# 04_POWER.net
KiCad netlist of a schematic drawn in Altium Designer
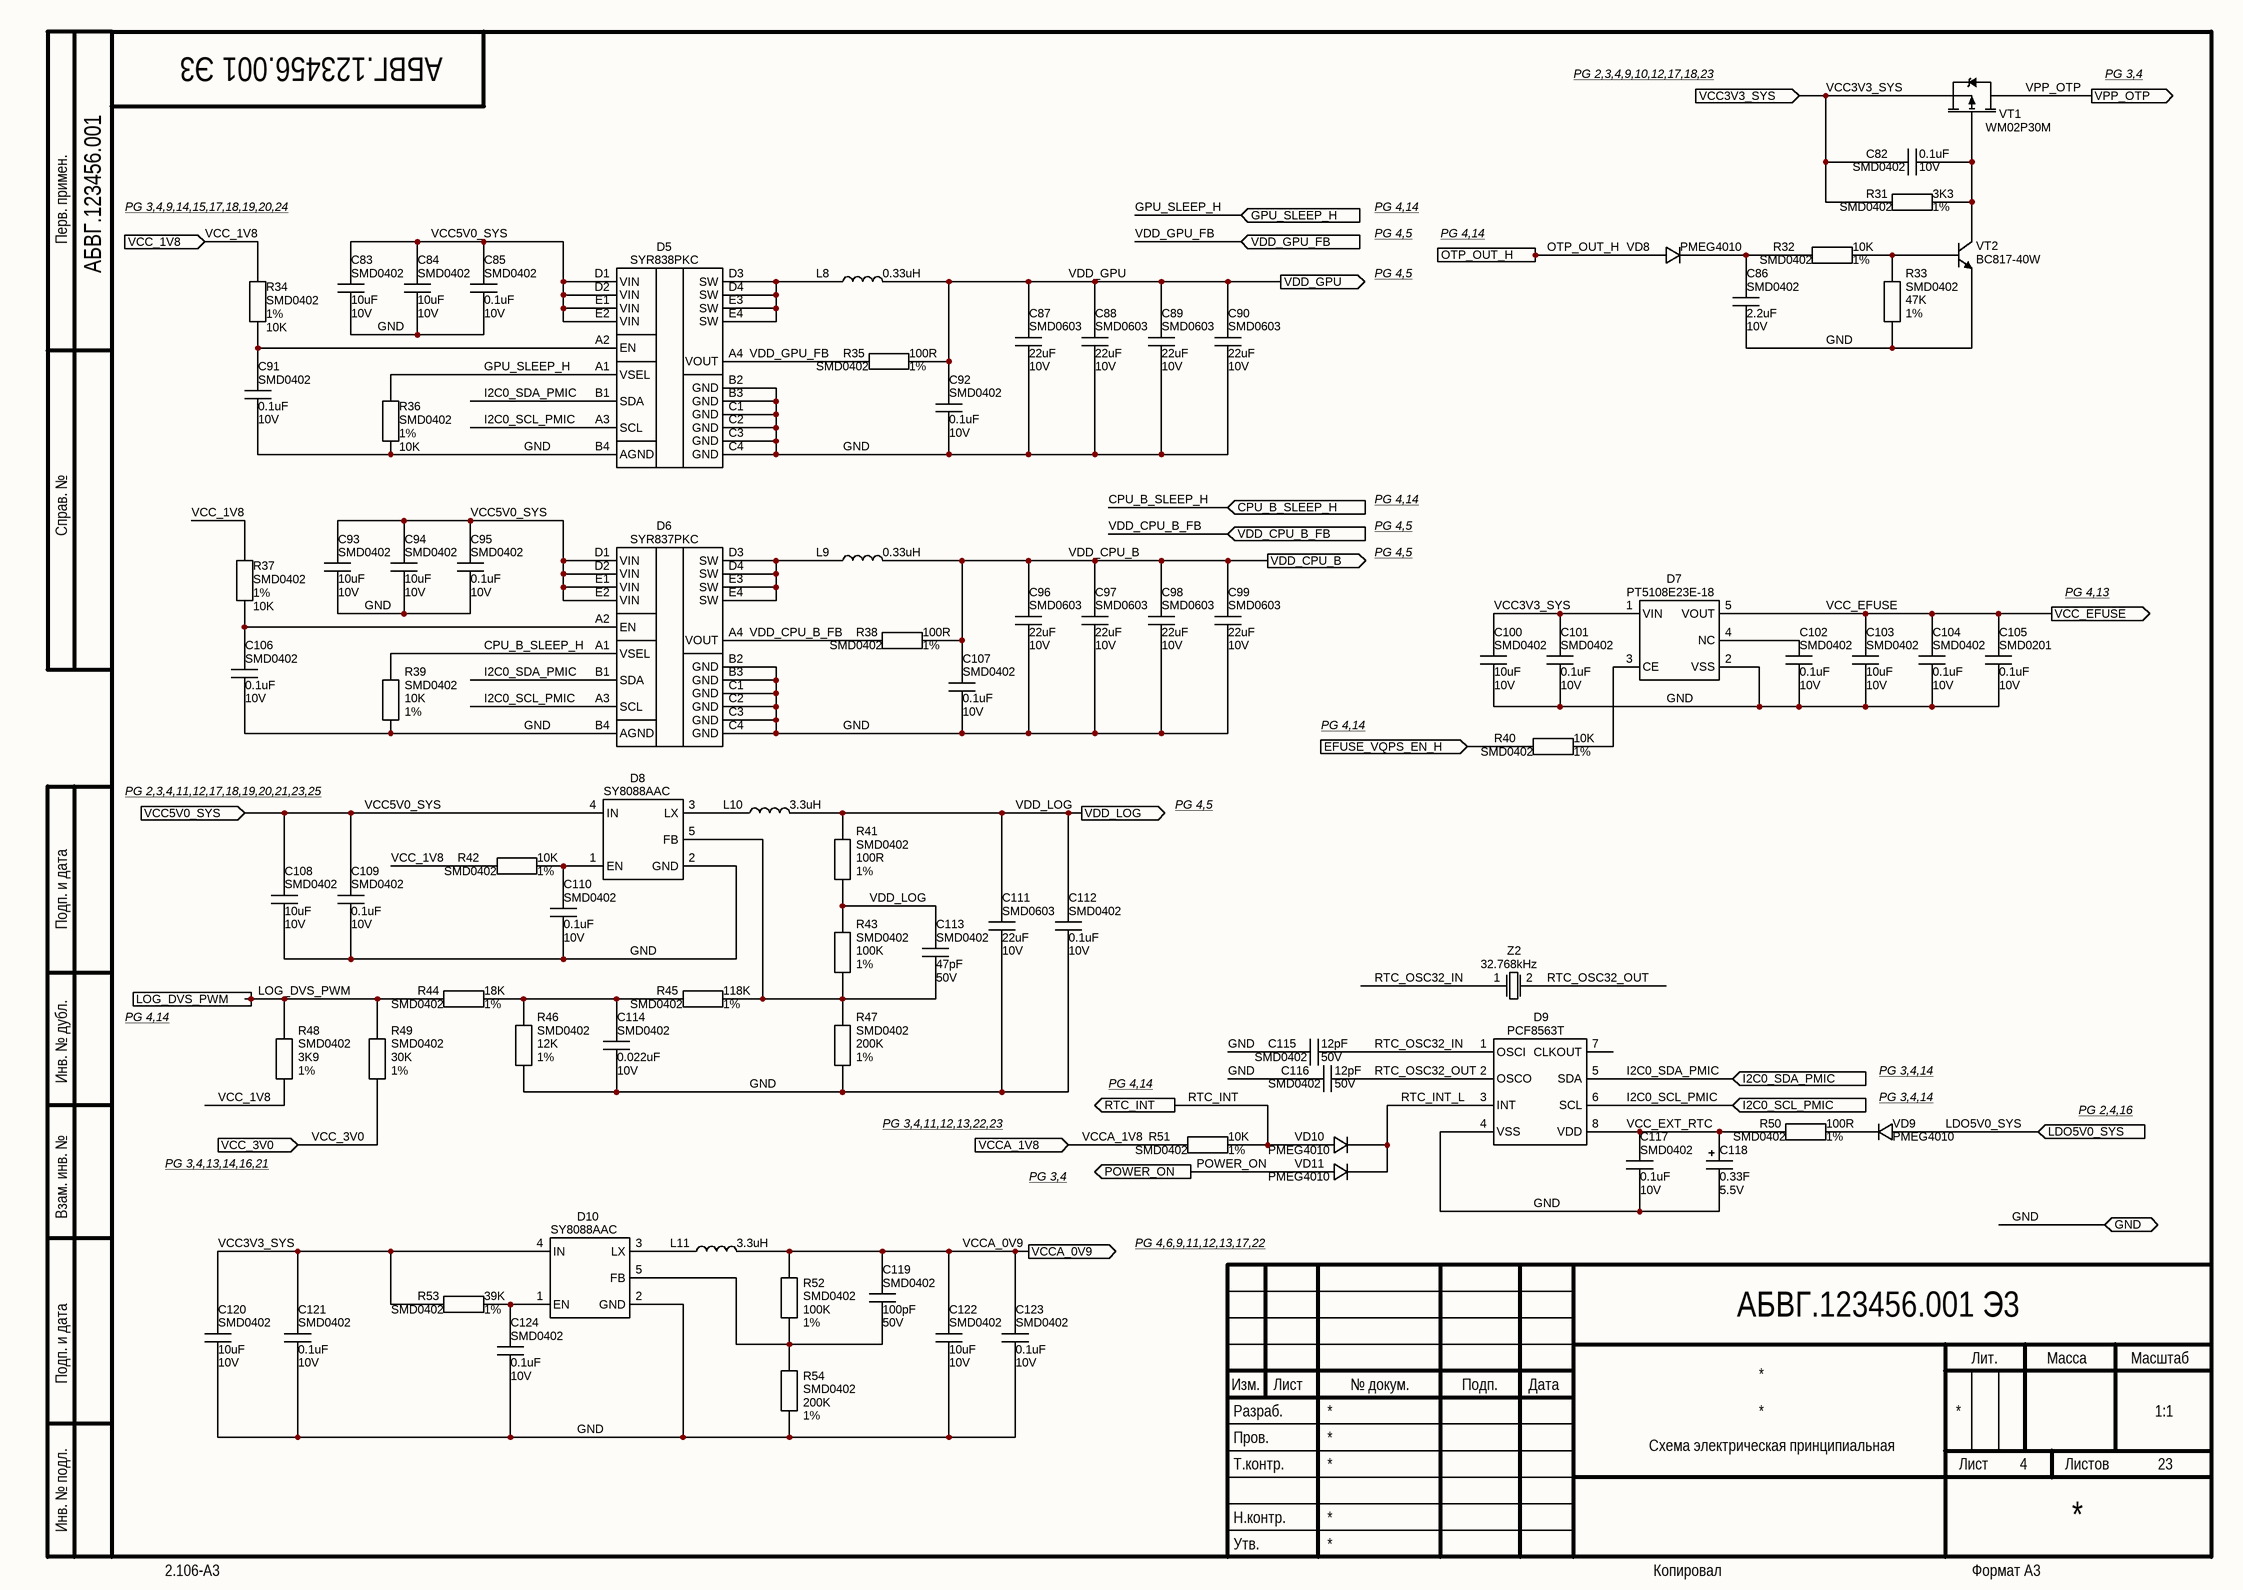
[diagram p0: 04 POWER.SchDoc]

(export (version "E")
  (design (tool "Eeschema 10.0.6"))
  (components
    (comp (ref "C82")
      (value "0.1uF")
      (footprint "Didur_PcbLib_1:CAP_SMD_0402")
      (fields
        (field (name "PACKAGE") "SMD0402")
        (field (name "PARTNUMBER") "CC0402KRX5R6BB104")
        (field (name "VOLTAGE") "10V")
      )
      (libsource (lib "Didur_SchLib_1") (part "Ceramic_Cap"))
    )
    (comp (ref "C83")
      (value "10uF")
      (footprint "Didur_PcbLib_1:CAP_SMD_0402")
      (fields
        (field (name "PACKAGE") "SMD0402")
        (field (name "PARTNUMBER") "CC0402MRX5R6BB106")
        (field (name "VOLTAGE") "10V")
      )
      (libsource (lib "Didur_SchLib_1") (part "Ceramic_Cap"))
    )
    (comp (ref "C84")
      (value "10uF")
      (footprint "Didur_PcbLib_1:CAP_SMD_0402")
      (fields
        (field (name "PACKAGE") "SMD0402")
        (field (name "PARTNUMBER") "CC0402MRX5R6BB106")
        (field (name "VOLTAGE") "10V")
      )
      (libsource (lib "Didur_SchLib_1") (part "Ceramic_Cap"))
    )
    (comp (ref "C85")
      (value "0.1uF")
      (footprint "Didur_PcbLib_1:CAP_SMD_0402")
      (fields
        (field (name "PACKAGE") "SMD0402")
        (field (name "PARTNUMBER") "CC0402KRX5R6BB104")
        (field (name "VOLTAGE") "10V")
      )
      (libsource (lib "Didur_SchLib_1") (part "Ceramic_Cap"))
    )
    (comp (ref "C86")
      (value "2.2uF")
      (footprint "Didur_PcbLib_1:CAP_SMD_0402")
      (fields
        (field (name "PACKAGE") "SMD0402")
        (field (name "PARTNUMBER") "CC0402KRX5R6BB225")
        (field (name "VOLTAGE") "10V")
      )
      (libsource (lib "Didur_SchLib_1") (part "Ceramic_Cap"))
    )
    (comp (ref "C87")
      (value "22uF")
      (footprint "CAP_SMD_0603")
      (fields
        (field (name "PACKAGE") "SMD0603")
        (field (name "PARTNUMBER") "CL10A226MP8NUNE")
        (field (name "VOLTAGE") "10V")
      )
      (libsource (lib "Didur_SchLib_1") (part "Ceramic_Cap"))
    )
    (comp (ref "C88")
      (value "22uF")
      (footprint "CAP_SMD_0603")
      (fields
        (field (name "PACKAGE") "SMD0603")
        (field (name "PARTNUMBER") "CL10A226MP8NUNE")
        (field (name "VOLTAGE") "10V")
      )
      (libsource (lib "Didur_SchLib_1") (part "Ceramic_Cap"))
    )
    (comp (ref "C89")
      (value "22uF")
      (footprint "CAP_SMD_0603")
      (fields
        (field (name "PACKAGE") "SMD0603")
        (field (name "PARTNUMBER") "CL10A226MP8NUNE")
        (field (name "VOLTAGE") "10V")
      )
      (libsource (lib "Didur_SchLib_1") (part "Ceramic_Cap"))
    )
    (comp (ref "C90")
      (value "22uF")
      (footprint "CAP_SMD_0603")
      (fields
        (field (name "PACKAGE") "SMD0603")
        (field (name "PARTNUMBER") "CL10A226MP8NUNE")
        (field (name "VOLTAGE") "10V")
      )
      (libsource (lib "Didur_SchLib_1") (part "Ceramic_Cap"))
    )
    (comp (ref "C91")
      (value "0.1uF")
      (footprint "Didur_PcbLib_1:CAP_SMD_0402")
      (fields
        (field (name "PACKAGE") "SMD0402")
        (field (name "PARTNUMBER") "CC0402KRX5R6BB104")
        (field (name "VOLTAGE") "10V")
      )
      (libsource (lib "Didur_SchLib_1") (part "Ceramic_Cap"))
    )
    (comp (ref "C92")
      (value "0.1uF")
      (footprint "Didur_PcbLib_1:CAP_SMD_0402")
      (fields
        (field (name "PACKAGE") "SMD0402")
        (field (name "PARTNUMBER") "CC0402KRX5R6BB104")
        (field (name "VOLTAGE") "10V")
      )
      (libsource (lib "Didur_SchLib_1") (part "Ceramic_Cap"))
    )
    (comp (ref "C93")
      (value "10uF")
      (footprint "Didur_PcbLib_1:CAP_SMD_0402")
      (fields
        (field (name "PACKAGE") "SMD0402")
        (field (name "PARTNUMBER") "CC0402MRX5R6BB106")
        (field (name "VOLTAGE") "10V")
      )
      (libsource (lib "Didur_SchLib_1") (part "Ceramic_Cap"))
    )
    (comp (ref "C94")
      (value "10uF")
      (footprint "Didur_PcbLib_1:CAP_SMD_0402")
      (fields
        (field (name "PACKAGE") "SMD0402")
        (field (name "PARTNUMBER") "CC0402MRX5R6BB106")
        (field (name "VOLTAGE") "10V")
      )
      (libsource (lib "Didur_SchLib_1") (part "Ceramic_Cap"))
    )
    (comp (ref "C95")
      (value "0.1uF")
      (footprint "Didur_PcbLib_1:CAP_SMD_0402")
      (fields
        (field (name "PACKAGE") "SMD0402")
        (field (name "PARTNUMBER") "CC0402KRX5R6BB104")
        (field (name "VOLTAGE") "10V")
      )
      (libsource (lib "Didur_SchLib_1") (part "Ceramic_Cap"))
    )
    (comp (ref "C96")
      (value "22uF")
      (footprint "CAP_SMD_0603")
      (fields
        (field (name "PACKAGE") "SMD0603")
        (field (name "PARTNUMBER") "CL10A226MP8NUNE")
        (field (name "VOLTAGE") "10V")
      )
      (libsource (lib "Didur_SchLib_1") (part "Ceramic_Cap"))
    )
    (comp (ref "C97")
      (value "22uF")
      (footprint "CAP_SMD_0603")
      (fields
        (field (name "PACKAGE") "SMD0603")
        (field (name "PARTNUMBER") "CL10A226MP8NUNE")
        (field (name "VOLTAGE") "10V")
      )
      (libsource (lib "Didur_SchLib_1") (part "Ceramic_Cap"))
    )
    (comp (ref "C98")
      (value "22uF")
      (footprint "CAP_SMD_0603")
      (fields
        (field (name "PACKAGE") "SMD0603")
        (field (name "PARTNUMBER") "CL10A226MP8NUNE")
        (field (name "VOLTAGE") "10V")
      )
      (libsource (lib "Didur_SchLib_1") (part "Ceramic_Cap"))
    )
    (comp (ref "C99")
      (value "22uF")
      (footprint "CAP_SMD_0603")
      (fields
        (field (name "PACKAGE") "SMD0603")
        (field (name "PARTNUMBER") "CL10A226MP8NUNE")
        (field (name "VOLTAGE") "10V")
      )
      (libsource (lib "Didur_SchLib_1") (part "Ceramic_Cap"))
    )
    (comp (ref "C100")
      (value "10uF")
      (footprint "Didur_PcbLib_1:CAP_SMD_0402")
      (fields
        (field (name "PACKAGE") "SMD0402")
        (field (name "PARTNUMBER") "CC0402MRX5R6BB106")
        (field (name "VOLTAGE") "10V")
      )
      (libsource (lib "Didur_SchLib_1") (part "Ceramic_Cap"))
    )
    (comp (ref "C101")
      (value "0.1uF")
      (footprint "Didur_PcbLib_1:CAP_SMD_0402")
      (fields
        (field (name "PACKAGE") "SMD0402")
        (field (name "PARTNUMBER") "CC0402KRX5R6BB104")
        (field (name "VOLTAGE") "10V")
      )
      (libsource (lib "Didur_SchLib_1") (part "Ceramic_Cap"))
    )
    (comp (ref "C102")
      (value "0.1uF")
      (footprint "Didur_PcbLib_1:CAP_SMD_0402")
      (fields
        (field (name "PACKAGE") "SMD0402")
        (field (name "PARTNUMBER") "CC0402KRX5R6BB104")
        (field (name "VOLTAGE") "10V")
      )
      (libsource (lib "Didur_SchLib_1") (part "Ceramic_Cap"))
    )
    (comp (ref "C103")
      (value "10uF")
      (footprint "Didur_PcbLib_1:CAP_SMD_0402")
      (fields
        (field (name "PACKAGE") "SMD0402")
        (field (name "PARTNUMBER") "CC0402MRX5R6BB106")
        (field (name "VOLTAGE") "10V")
      )
      (libsource (lib "Didur_SchLib_1") (part "Ceramic_Cap"))
    )
    (comp (ref "C104")
      (value "0.1uF")
      (footprint "Didur_PcbLib_1:CAP_SMD_0402")
      (fields
        (field (name "PACKAGE") "SMD0402")
        (field (name "PARTNUMBER") "CC0402KRX5R6BB104")
        (field (name "VOLTAGE") "10V")
      )
      (libsource (lib "Didur_SchLib_1") (part "Ceramic_Cap"))
    )
    (comp (ref "C105")
      (value "0.1uF")
      (footprint "Didur_PcbLib_1:CAP_SMD_0201")
      (fields
        (field (name "PACKAGE") "SMD0201")
        (field (name "PARTNUMBER") "CC0201KRX5R6BB104")
        (field (name "VOLTAGE") "10V")
      )
      (libsource (lib "Didur_SchLib_1") (part "Ceramic_Cap"))
    )
    (comp (ref "C106")
      (value "0.1uF")
      (footprint "Didur_PcbLib_1:CAP_SMD_0402")
      (fields
        (field (name "PACKAGE") "SMD0402")
        (field (name "PARTNUMBER") "CC0402KRX5R6BB104")
        (field (name "VOLTAGE") "10V")
      )
      (libsource (lib "Didur_SchLib_1") (part "Ceramic_Cap"))
    )
    (comp (ref "C107")
      (value "0.1uF")
      (footprint "Didur_PcbLib_1:CAP_SMD_0402")
      (fields
        (field (name "PACKAGE") "SMD0402")
        (field (name "PARTNUMBER") "CC0402KRX5R6BB104")
        (field (name "VOLTAGE") "10V")
      )
      (libsource (lib "Didur_SchLib_1") (part "Ceramic_Cap"))
    )
    (comp (ref "C108")
      (value "10uF")
      (footprint "Didur_PcbLib_1:CAP_SMD_0402")
      (fields
        (field (name "PACKAGE") "SMD0402")
        (field (name "PARTNUMBER") "CC0402MRX5R6BB106")
        (field (name "VOLTAGE") "10V")
      )
      (libsource (lib "Didur_SchLib_1") (part "Ceramic_Cap"))
    )
    (comp (ref "C109")
      (value "0.1uF")
      (footprint "Didur_PcbLib_1:CAP_SMD_0402")
      (fields
        (field (name "PACKAGE") "SMD0402")
        (field (name "PARTNUMBER") "CC0402KRX5R6BB104")
        (field (name "VOLTAGE") "10V")
      )
      (libsource (lib "Didur_SchLib_1") (part "Ceramic_Cap"))
    )
    (comp (ref "C110")
      (value "0.1uF")
      (footprint "Didur_PcbLib_1:CAP_SMD_0402")
      (fields
        (field (name "PACKAGE") "SMD0402")
        (field (name "PARTNUMBER") "CC0402KRX5R6BB104")
        (field (name "VOLTAGE") "10V")
      )
      (libsource (lib "Didur_SchLib_1") (part "Ceramic_Cap"))
    )
    (comp (ref "C111")
      (value "22uF")
      (footprint "CAP_SMD_0603")
      (fields
        (field (name "PACKAGE") "SMD0603")
        (field (name "PARTNUMBER") "CL10A226MP8NUNE")
        (field (name "VOLTAGE") "10V")
      )
      (libsource (lib "Didur_SchLib_1") (part "Ceramic_Cap"))
    )
    (comp (ref "C112")
      (value "0.1uF")
      (footprint "Didur_PcbLib_1:CAP_SMD_0402")
      (fields
        (field (name "PACKAGE") "SMD0402")
        (field (name "PARTNUMBER") "CC0402KRX5R6BB104")
        (field (name "VOLTAGE") "10V")
      )
      (libsource (lib "Didur_SchLib_1") (part "Ceramic_Cap"))
    )
    (comp (ref "C113")
      (value "47pF")
      (footprint "Didur_PcbLib_1:CAP_SMD_0402")
      (fields
        (field (name "PACKAGE") "SMD0402")
        (field (name "PARTNUMBER") "CC0402FRNPO9BN470")
        (field (name "VOLTAGE") "50V")
      )
      (libsource (lib "Didur_SchLib_1") (part "Ceramic_Cap"))
    )
    (comp (ref "C114")
      (value "0.022uF")
      (footprint "Didur_PcbLib_1:CAP_SMD_0402")
      (fields
        (field (name "PACKAGE") "SMD0402")
        (field (name "PARTNUMBER") "GRM155R61A223KA01D")
        (field (name "VOLTAGE") "10V")
      )
      (libsource (lib "Didur_SchLib_1") (part "Ceramic_Cap"))
    )
    (comp (ref "C115")
      (value "12pF")
      (footprint "Didur_PcbLib_1:CAP_SMD_0402")
      (fields
        (field (name "PACKAGE") "SMD0402")
        (field (name "PARTNUMBER") "CC0402JRNPO9BN120")
        (field (name "VOLTAGE") "50V")
      )
      (libsource (lib "Didur_SchLib_1") (part "Ceramic_Cap"))
    )
    (comp (ref "C116")
      (value "12pF")
      (footprint "Didur_PcbLib_1:CAP_SMD_0402")
      (fields
        (field (name "PACKAGE") "SMD0402")
        (field (name "PARTNUMBER") "CC0402JRNPO9BN120")
        (field (name "VOLTAGE") "50V")
      )
      (libsource (lib "Didur_SchLib_1") (part "Ceramic_Cap"))
    )
    (comp (ref "C117")
      (value "0.1uF")
      (footprint "Didur_PcbLib_1:CAP_SMD_0402")
      (fields
        (field (name "PACKAGE") "SMD0402")
        (field (name "PARTNUMBER") "CC0402KRX5R6BB104")
        (field (name "VOLTAGE") "10V")
      )
      (libsource (lib "Didur_SchLib_1") (part "Ceramic_Cap"))
    )
    (comp (ref "C118")
      (value "0.33F")
      (footprint "Didur_PcbLib_1:DCS5R5_H")
      (fields
        (field (name "PARTNUMBER") "DCS5R5334HF")
        (field (name "TOLERANCE") "±20%")
        (field (name "VOLTAGE") "5.5V")
      )
      (libsource (lib "Didur_SchLib_1") (part "AluminiumCap"))
    )
    (comp (ref "C119")
      (value "100pF")
      (footprint "Didur_PcbLib_1:CAP_SMD_0402")
      (fields
        (field (name "PACKAGE") "SMD0402")
        (field (name "PARTNUMBER") "CC0402KRNPO9BN101")
        (field (name "VOLTAGE") "50V")
      )
      (libsource (lib "Didur_SchLib_1") (part "Ceramic_Cap"))
    )
    (comp (ref "C120")
      (value "10uF")
      (footprint "Didur_PcbLib_1:CAP_SMD_0402")
      (fields
        (field (name "PACKAGE") "SMD0402")
        (field (name "PARTNUMBER") "CC0402MRX5R6BB106")
        (field (name "VOLTAGE") "10V")
      )
      (libsource (lib "Didur_SchLib_1") (part "Ceramic_Cap"))
    )
    (comp (ref "C121")
      (value "0.1uF")
      (footprint "Didur_PcbLib_1:CAP_SMD_0402")
      (fields
        (field (name "PACKAGE") "SMD0402")
        (field (name "PARTNUMBER") "CC0402KRX5R6BB104")
        (field (name "VOLTAGE") "10V")
      )
      (libsource (lib "Didur_SchLib_1") (part "Ceramic_Cap"))
    )
    (comp (ref "C122")
      (value "10uF")
      (footprint "Didur_PcbLib_1:CAP_SMD_0402")
      (fields
        (field (name "PACKAGE") "SMD0402")
        (field (name "PARTNUMBER") "CC0402MRX5R6BB106")
        (field (name "VOLTAGE") "10V")
      )
      (libsource (lib "Didur_SchLib_1") (part "Ceramic_Cap"))
    )
    (comp (ref "C123")
      (value "0.1uF")
      (footprint "Didur_PcbLib_1:CAP_SMD_0402")
      (fields
        (field (name "PACKAGE") "SMD0402")
        (field (name "PARTNUMBER") "CC0402KRX5R6BB104")
        (field (name "VOLTAGE") "10V")
      )
      (libsource (lib "Didur_SchLib_1") (part "Ceramic_Cap"))
    )
    (comp (ref "C124")
      (value "0.1uF")
      (footprint "Didur_PcbLib_1:CAP_SMD_0402")
      (fields
        (field (name "PACKAGE") "SMD0402")
        (field (name "PARTNUMBER") "CC0402KRX5R6BB104")
        (field (name "VOLTAGE") "10V")
      )
      (libsource (lib "Didur_SchLib_1") (part "Ceramic_Cap"))
    )
    (comp (ref "D5")
      (value "SYR838PKC")
      (footprint "Didur_PcbLib_1:WLCSP-20")
      (libsource (lib "Didur_SchLib_1") (part "SYR838PKC"))
    )
    (comp (ref "D6")
      (value "SYR837PKC")
      (footprint "Didur_PcbLib_1:WLCSP-20")
      (libsource (lib "Didur_SchLib_1") (part "SYR838PKC"))
    )
    (comp (ref "D7")
      (value "PT5108E23E-18")
      (footprint "Didur_PcbLib_1:SOT23-5")
      (libsource (lib "Didur_SchLib_1") (part "PT5108E23E-30"))
    )
    (comp (ref "D8")
      (value "SY8088AAC")
      (footprint "Didur_PcbLib_1:SOT23-5")
      (libsource (lib "Didur_SchLib_1") (part "SY8088AAC"))
    )
    (comp (ref "D9")
      (value "PCF8563T")
      (footprint "Didur_PcbLib_1:SO8")
      (libsource (lib "Didur_SchLib_1") (part "PCF8563T"))
    )
    (comp (ref "D10")
      (value "SY8088AAC")
      (footprint "Didur_PcbLib_1:SOT23-5")
      (libsource (lib "Didur_SchLib_1") (part "SY8088AAC"))
    )
    (comp (ref "L8")
      (value "0.33uH")
      (footprint "Didur_PcbLib_1:HEI252012A")
      (fields (field (name "PARTNUMBER") "HEI252012A-R33M-Q8") (field (name "Comment") "Value"))
      (libsource (lib "Didur_SchLib_1") (part "Inductor_smal"))
    )
    (comp (ref "L9")
      (value "0.33uH")
      (footprint "Didur_PcbLib_1:HEI252012A")
      (fields (field (name "PARTNUMBER") "HEI252012A-R33M-Q8") (field (name "Comment") "Value"))
      (libsource (lib "Didur_SchLib_1") (part "Inductor_smal"))
    )
    (comp (ref "L10")
      (value "3.3uH")
      (footprint "Didur_PcbLib_1:HEI252012A")
      (fields (field (name "PARTNUMBER") "WPN252012H3R3MT") (field (name "Comment") "Value"))
      (libsource (lib "Didur_SchLib_1") (part "Inductor_smal"))
    )
    (comp (ref "L11")
      (value "3.3uH")
      (footprint "Didur_PcbLib_1:HEI252012A")
      (fields (field (name "PARTNUMBER") "WPN252012H3R3MT") (field (name "Comment") "Value"))
      (libsource (lib "Didur_SchLib_1") (part "Inductor_smal"))
    )
    (comp (ref "R31")
      (value "3K3")
      (footprint "Didur_PcbLib_1:RES_SMD_0402")
      (fields
        (field (name "PACKAGE") "SMD0402")
        (field (name "PARTNUMBER") "RC0402FR-073K3L")
        (field (name "TOLERANCE") "1%")
      )
      (libsource (lib "Didur_SchLib_1") (part "Chip_Res"))
    )
    (comp (ref "R32")
      (value "10K")
      (footprint "Didur_PcbLib_1:RES_SMD_0402")
      (fields
        (field (name "PACKAGE") "SMD0402")
        (field (name "PARTNUMBER") "RC0402FR-0710KL")
        (field (name "TOLERANCE") "1%")
      )
      (libsource (lib "") (part "Chip_Res_1"))
    )
    (comp (ref "R33")
      (value "47K")
      (footprint "Didur_PcbLib_1:RES_SMD_0402")
      (fields
        (field (name "PACKAGE") "SMD0402")
        (field (name "PARTNUMBER") "RC0402FR-1347KL")
        (field (name "TOLERANCE") "1%")
      )
      (libsource (lib "Didur_SchLib_1") (part "Chip_Res"))
    )
    (comp (ref "R34")
      (value "10K")
      (footprint "Didur_PcbLib_1:RES_SMD_0402")
      (fields
        (field (name "PACKAGE") "SMD0402")
        (field (name "PARTNUMBER") "RC0402FR-0710KL")
        (field (name "TOLERANCE") "1%")
      )
      (libsource (lib "") (part "Chip_Res_2"))
    )
    (comp (ref "R35")
      (value "100R")
      (footprint "Didur_PcbLib_1:RES_SMD_0402")
      (fields
        (field (name "PACKAGE") "SMD0402")
        (field (name "PARTNUMBER") "RC0402FR-07100RL")
        (field (name "TOLERANCE") "1%")
      )
      (libsource (lib "Didur_SchLib_1") (part "Chip_Res"))
    )
    (comp (ref "R36")
      (value "10K")
      (footprint "Didur_PcbLib_1:RES_SMD_0402")
      (fields
        (field (name "PACKAGE") "SMD0402")
        (field (name "PARTNUMBER") "RC0402FR-0710KL")
        (field (name "TOLERANCE") "1%")
      )
      (libsource (lib "") (part "Chip_Res_2"))
    )
    (comp (ref "R37")
      (value "10K")
      (footprint "Didur_PcbLib_1:RES_SMD_0402")
      (fields
        (field (name "PACKAGE") "SMD0402")
        (field (name "PARTNUMBER") "RC0402FR-0710KL")
        (field (name "TOLERANCE") "1%")
      )
      (libsource (lib "") (part "Chip_Res_2"))
    )
    (comp (ref "R38")
      (value "100R")
      (footprint "Didur_PcbLib_1:RES_SMD_0402")
      (fields
        (field (name "PACKAGE") "SMD0402")
        (field (name "PARTNUMBER") "RC0402FR-07100RL")
        (field (name "TOLERANCE") "1%")
      )
      (libsource (lib "Didur_SchLib_1") (part "Chip_Res"))
    )
    (comp (ref "R39")
      (value "10K")
      (footprint "Didur_PcbLib_1:RES_SMD_0402")
      (fields
        (field (name "PACKAGE") "SMD0402")
        (field (name "PARTNUMBER") "RC0402FR-0710KL")
        (field (name "TOLERANCE") "1%")
      )
      (libsource (lib "") (part "Chip_Res_2"))
    )
    (comp (ref "R40")
      (value "10K")
      (footprint "Didur_PcbLib_1:RES_SMD_0402")
      (fields
        (field (name "PACKAGE") "SMD0402")
        (field (name "PARTNUMBER") "RC0402FR-0710KL")
        (field (name "TOLERANCE") "1%")
      )
      (libsource (lib "") (part "Chip_Res_1"))
    )
    (comp (ref "R41")
      (value "100R")
      (footprint "Didur_PcbLib_1:RES_SMD_0402")
      (fields
        (field (name "PACKAGE") "SMD0402")
        (field (name "PARTNUMBER") "RC0402FR-07100RL")
        (field (name "TOLERANCE") "1%")
      )
      (libsource (lib "") (part "Chip_Res_2"))
    )
    (comp (ref "R42")
      (value "10K")
      (footprint "Didur_PcbLib_1:RES_SMD_0402")
      (fields
        (field (name "PACKAGE") "SMD0402")
        (field (name "PARTNUMBER") "RC0402FR-0710KL")
        (field (name "TOLERANCE") "1%")
      )
      (libsource (lib "") (part "Chip_Res_1"))
    )
    (comp (ref "R43")
      (value "100K")
      (footprint "Didur_PcbLib_1:RES_SMD_0402")
      (fields
        (field (name "PACKAGE") "SMD0402")
        (field (name "PARTNUMBER") "RC0402FR-07100KL")
        (field (name "TOLERANCE") "1%")
      )
      (libsource (lib "Didur_SchLib_1") (part "Chip_Res"))
    )
    (comp (ref "R44")
      (value "18K")
      (footprint "Didur_PcbLib_1:RES_SMD_0402")
      (fields
        (field (name "PACKAGE") "SMD0402")
        (field (name "PARTNUMBER") "RC0402FR-0718KL")
        (field (name "TOLERANCE") "1%")
      )
      (libsource (lib "Didur_SchLib_1") (part "Chip_Res"))
    )
    (comp (ref "R45")
      (value "118K")
      (footprint "Didur_PcbLib_1:RES_SMD_0402")
      (fields
        (field (name "PACKAGE") "SMD0402")
        (field (name "PARTNUMBER") "RC0402FR-07118KL")
        (field (name "TOLERANCE") "1%")
      )
      (libsource (lib "Didur_SchLib_1") (part "Chip_Res"))
    )
    (comp (ref "R46")
      (value "12K")
      (footprint "Didur_PcbLib_1:RES_SMD_0402")
      (fields
        (field (name "PACKAGE") "SMD0402")
        (field (name "PARTNUMBER") "RC0402FR-0712KL")
        (field (name "TOLERANCE") "1%")
      )
      (libsource (lib "Didur_SchLib_1") (part "Chip_Res"))
    )
    (comp (ref "R47")
      (value "200K")
      (footprint "Didur_PcbLib_1:RES_SMD_0402")
      (fields
        (field (name "PACKAGE") "SMD0402")
        (field (name "PARTNUMBER") "RC0402FR-07200KL")
        (field (name "TOLERANCE") "1%")
      )
      (libsource (lib "Didur_SchLib_1") (part "Chip_Res"))
    )
    (comp (ref "R48")
      (value "3K9")
      (footprint "Didur_PcbLib_1:RES_SMD_0402")
      (fields
        (field (name "PACKAGE") "SMD0402")
        (field (name "PARTNUMBER") "RC0402FR-073K9L")
        (field (name "TOLERANCE") "1%")
      )
      (libsource (lib "Didur_SchLib_1") (part "Chip_Res"))
    )
    (comp (ref "R49")
      (value "30K")
      (footprint "Didur_PcbLib_1:RES_SMD_0402")
      (fields
        (field (name "PACKAGE") "SMD0402")
        (field (name "PARTNUMBER") "RC0402FR-0730KL")
        (field (name "TOLERANCE") "1%")
      )
      (libsource (lib "Didur_SchLib_1") (part "Chip_Res"))
    )
    (comp (ref "R50")
      (value "100R")
      (footprint "Didur_PcbLib_1:RES_SMD_0402")
      (fields
        (field (name "PACKAGE") "SMD0402")
        (field (name "PARTNUMBER") "RC0402FR-07100RL")
        (field (name "TOLERANCE") "1%")
      )
      (libsource (lib "Didur_SchLib_1") (part "Chip_Res"))
    )
    (comp (ref "R51")
      (value "10K")
      (footprint "Didur_PcbLib_1:RES_SMD_0402")
      (fields
        (field (name "PACKAGE") "SMD0402")
        (field (name "PARTNUMBER") "RC0402FR-0710KL")
        (field (name "TOLERANCE") "1%")
      )
      (libsource (lib "") (part "Chip_Res_1"))
    )
    (comp (ref "R52")
      (value "100K")
      (footprint "Didur_PcbLib_1:RES_SMD_0402")
      (fields
        (field (name "PACKAGE") "SMD0402")
        (field (name "PARTNUMBER") "RC0402FR-07100KL")
        (field (name "TOLERANCE") "1%")
      )
      (libsource (lib "Didur_SchLib_1") (part "Chip_Res"))
    )
    (comp (ref "R53")
      (value "39K")
      (footprint "Didur_PcbLib_1:RES_SMD_0402")
      (fields
        (field (name "PACKAGE") "SMD0402")
        (field (name "PARTNUMBER") "RC0402FR-0739KL")
        (field (name "TOLERANCE") "1%")
      )
      (libsource (lib "Didur_SchLib_1") (part "Chip_Res"))
    )
    (comp (ref "R54")
      (value "200K")
      (footprint "Didur_PcbLib_1:RES_SMD_0402")
      (fields
        (field (name "PACKAGE") "SMD0402")
        (field (name "PARTNUMBER") "RC0402FR-07200KL")
        (field (name "TOLERANCE") "1%")
      )
      (libsource (lib "Didur_SchLib_1") (part "Chip_Res"))
    )
    (comp (ref "VD8")
      (value "PMEG4010")
      (footprint "SOD323")
      (fields (field (name "PARTNUMBER") "PMEG4010CEJ.115") (field (name "Comment") "Diode"))
      (libsource (lib "Didur_SchLib_1") (part "Diode"))
    )
    (comp (ref "VD9")
      (value "PMEG4010")
      (footprint "SOD323")
      (fields (field (name "PARTNUMBER") "PMEG4010CEJ.115") (field (name "Comment") "Diode"))
      (libsource (lib "Didur_SchLib_1") (part "Diode"))
    )
    (comp (ref "VD10")
      (value "PMEG4010")
      (footprint "SOD323")
      (fields (field (name "PARTNUMBER") "PMEG4010CEJ.115") (field (name "Comment") "Diode"))
      (libsource (lib "Didur_SchLib_1") (part "Diode"))
    )
    (comp (ref "VD11")
      (value "PMEG4010")
      (footprint "SOD323")
      (fields (field (name "PARTNUMBER") "PMEG4010CEJ.115") (field (name "Comment") "Diode"))
      (libsource (lib "Didur_SchLib_1") (part "Diode"))
    )
    (comp (ref "VT1")
      (value "WM02P30M")
      (footprint "SOT23")
      (fields (field (name "Comment") "Value"))
      (libsource (lib "Didur_SchLib_1") (part "MOSFET_P"))
    )
    (comp (ref "VT2")
      (value "BC817-40W")
      (footprint "Didur_PcbLib_1:SC-70")
      (libsource (lib "Didur_SchLib_1") (part "NPN_BEC"))
    )
    (comp (ref "Z2")
      (value "32.768kHz")
      (footprint "Didur_PcbLib_1:TSX3215")
      (fields (field (name "PARTNUMBER") "SJK-7L-32.768-12.5-20-70-C") (field (name "Comment") "Value"))
      (libsource (lib "Didur_SchLib_1") (part "OSC3215"))
    )
  )
  (nets
    (net (code "1") (name "/CPU_B_SLEEP_H") (class "Default")
      (node (ref "D6") (pin "A1") (pinfunction "VSEL_A1") (pintype "passive"))
      (node (ref "R39") (pin "2") (pinfunction "2_2") (pintype "passive"))
    )
    (net (code "2") (name "/EFUSE_VQPS_EN_H") (class "Default")
      (node (ref "R40") (pin "2") (pinfunction "2_2") (pintype "passive"))
    )
    (net (code "3") (name "/GND") (class "Default")
      (node (ref "C100") (pin "2") (pinfunction "2_2") (pintype "power_in"))
      (node (ref "C101") (pin "2") (pinfunction "2_2") (pintype "power_in"))
      (node (ref "C102") (pin "2") (pinfunction "2_2") (pintype "power_in"))
      (node (ref "C103") (pin "2") (pinfunction "2_2") (pintype "power_in"))
      (node (ref "C104") (pin "2") (pinfunction "2_2") (pintype "power_in"))
      (node (ref "C105") (pin "2") (pinfunction "2_2") (pintype "power_in"))
      (node (ref "C106") (pin "2") (pinfunction "2_2") (pintype "power_in"))
      (node (ref "C107") (pin "2") (pinfunction "2_2") (pintype "power_in"))
      (node (ref "C108") (pin "2") (pinfunction "2_2") (pintype "power_in"))
      (node (ref "C109") (pin "2") (pinfunction "2_2") (pintype "power_in"))
      (node (ref "C110") (pin "2") (pinfunction "2_2") (pintype "power_in"))
      (node (ref "C111") (pin "1") (pinfunction "1_1") (pintype "power_in"))
      (node (ref "C112") (pin "2") (pinfunction "2_2") (pintype "power_in"))
      (node (ref "C114") (pin "2") (pinfunction "2_2") (pintype "power_in"))
      (node (ref "C115") (pin "2") (pinfunction "2_2") (pintype "power_in"))
      (node (ref "C116") (pin "2") (pinfunction "2_2") (pintype "power_in"))
      (node (ref "C117") (pin "2") (pinfunction "2_2") (pintype "power_in"))
      (node (ref "C118") (pin "2") (pinfunction "2_2") (pintype "power_in"))
      (node (ref "C120") (pin "2") (pinfunction "2_2") (pintype "power_in"))
      (node (ref "C121") (pin "2") (pinfunction "2_2") (pintype "power_in"))
      (node (ref "C122") (pin "2") (pinfunction "2_2") (pintype "power_in"))
      (node (ref "C123") (pin "2") (pinfunction "2_2") (pintype "power_in"))
      (node (ref "C124") (pin "2") (pinfunction "2_2") (pintype "power_in"))
      (node (ref "C83") (pin "2") (pinfunction "2_2") (pintype "power_in"))
      (node (ref "C84") (pin "2") (pinfunction "2_2") (pintype "power_in"))
      (node (ref "C85") (pin "2") (pinfunction "2_2") (pintype "power_in"))
      (node (ref "C86") (pin "1") (pinfunction "1_1") (pintype "power_in"))
      (node (ref "C87") (pin "1") (pinfunction "1_1") (pintype "power_in"))
      (node (ref "C88") (pin "1") (pinfunction "1_1") (pintype "power_in"))
      (node (ref "C89") (pin "1") (pinfunction "1_1") (pintype "power_in"))
      (node (ref "C90") (pin "1") (pinfunction "1_1") (pintype "power_in"))
      (node (ref "C91") (pin "2") (pinfunction "2_2") (pintype "power_in"))
      (node (ref "C92") (pin "2") (pinfunction "2_2") (pintype "power_in"))
      (node (ref "C93") (pin "2") (pinfunction "2_2") (pintype "power_in"))
      (node (ref "C94") (pin "2") (pinfunction "2_2") (pintype "power_in"))
      (node (ref "C95") (pin "2") (pinfunction "2_2") (pintype "power_in"))
      (node (ref "C96") (pin "1") (pinfunction "1_1") (pintype "power_in"))
      (node (ref "C97") (pin "1") (pinfunction "1_1") (pintype "power_in"))
      (node (ref "C98") (pin "1") (pinfunction "1_1") (pintype "power_in"))
      (node (ref "C99") (pin "1") (pinfunction "1_1") (pintype "power_in"))
      (node (ref "D10") (pin "2") (pinfunction "GND_2") (pintype "passive"))
      (node (ref "D5") (pin "B2") (pinfunction "GND_B2") (pintype "passive"))
      (node (ref "D5") (pin "B3") (pinfunction "GND_B3") (pintype "passive"))
      (node (ref "D5") (pin "B4") (pinfunction "AGND_B4") (pintype "passive"))
      (node (ref "D5") (pin "C1") (pinfunction "GND_C1") (pintype "passive"))
      (node (ref "D5") (pin "C2") (pinfunction "GND_C2") (pintype "passive"))
      (node (ref "D5") (pin "C3") (pinfunction "GND_C3") (pintype "passive"))
      (node (ref "D5") (pin "C4") (pinfunction "GND_C4") (pintype "passive"))
      (node (ref "D6") (pin "B2") (pinfunction "GND_B2") (pintype "passive"))
      (node (ref "D6") (pin "B3") (pinfunction "GND_B3") (pintype "passive"))
      (node (ref "D6") (pin "B4") (pinfunction "AGND_B4") (pintype "passive"))
      (node (ref "D6") (pin "C1") (pinfunction "GND_C1") (pintype "passive"))
      (node (ref "D6") (pin "C2") (pinfunction "GND_C2") (pintype "passive"))
      (node (ref "D6") (pin "C3") (pinfunction "GND_C3") (pintype "passive"))
      (node (ref "D6") (pin "C4") (pinfunction "GND_C4") (pintype "passive"))
      (node (ref "D7") (pin "2") (pinfunction "VSS_2") (pintype "passive"))
      (node (ref "D8") (pin "2") (pinfunction "GND_2") (pintype "passive"))
      (node (ref "D9") (pin "4") (pinfunction "VSS_4") (pintype "passive"))
      (node (ref "R33") (pin "1") (pinfunction "1_1") (pintype "passive"))
      (node (ref "R36") (pin "1") (pinfunction "1_1") (pintype "passive"))
      (node (ref "R39") (pin "1") (pinfunction "1_1") (pintype "passive"))
      (node (ref "R46") (pin "1") (pinfunction "1_1") (pintype "passive"))
      (node (ref "R47") (pin "1") (pinfunction "1_1") (pintype "passive"))
      (node (ref "R54") (pin "1") (pinfunction "1_1") (pintype "passive"))
      (node (ref "VT2") (pin "2") (pinfunction "E_2") (pintype "passive"))
    )
    (net (code "4") (name "/GPU_SLEEP_H") (class "Default")
      (node (ref "D5") (pin "A1") (pinfunction "VSEL_A1") (pintype "passive"))
      (node (ref "R36") (pin "2") (pinfunction "2_2") (pintype "passive"))
    )
    (net (code "5") (name "/I2C0_SCL_PMIC") (class "Default")
      (node (ref "D5") (pin "A3") (pinfunction "SCL_A3") (pintype "passive"))
      (node (ref "D6") (pin "A3") (pinfunction "SCL_A3") (pintype "passive"))
      (node (ref "D9") (pin "6") (pinfunction "SCL_6") (pintype "passive"))
    )
    (net (code "6") (name "/I2C0_SDA_PMIC") (class "Default")
      (node (ref "D5") (pin "B1") (pinfunction "SDA_B1") (pintype "passive"))
      (node (ref "D6") (pin "B1") (pinfunction "SDA_B1") (pintype "passive"))
      (node (ref "D9") (pin "5") (pinfunction "SDA_5") (pintype "passive"))
    )
    (net (code "7") (name "/LDO5V0_SYS") (class "Default")
      (node (ref "VD9") (pin "1") (pinfunction "A_1") (pintype "passive"))
    )
    (net (code "8") (name "/LOG_DVS_PWM") (class "Default")
      (node (ref "R44") (pin "1") (pinfunction "1_1") (pintype "passive"))
      (node (ref "R48") (pin "2") (pinfunction "2_2") (pintype "passive"))
      (node (ref "R49") (pin "2") (pinfunction "2_2") (pintype "passive"))
    )
    (net (code "9") (name "/OTP_OUT_H") (class "Default")
      (node (ref "VD8") (pin "1") (pinfunction "A_1") (pintype "passive"))
    )
    (net (code "10") (name "/POWER_ON") (class "Default")
      (node (ref "VD11") (pin "1") (pinfunction "A_1") (pintype "passive"))
    )
    (net (code "11") (name "/RTC_INT") (class "Default")
      (node (ref "R51") (pin "1") (pinfunction "1_1") (pintype "passive"))
      (node (ref "VD10") (pin "1") (pinfunction "A_1") (pintype "passive"))
    )
    (net (code "12") (name "/RTC_INT_L") (class "Default")
      (node (ref "D9") (pin "3") (pinfunction "INT_3") (pintype "passive"))
      (node (ref "VD10") (pin "2") (pinfunction "C_2") (pintype "passive"))
      (node (ref "VD11") (pin "2") (pinfunction "C_2") (pintype "passive"))
    )
    (net (code "13") (name "/RTC_OSC32_IN") (class "Default")
      (node (ref "C115") (pin "1") (pinfunction "1_1") (pintype "power_in"))
      (node (ref "D9") (pin "1") (pinfunction "OSCI_1") (pintype "passive"))
      (node (ref "Z2") (pin "1") (pinfunction "1_1") (pintype "passive"))
    )
    (net (code "14") (name "/RTC_OSC32_OUT") (class "Default")
      (node (ref "C116") (pin "1") (pinfunction "1_1") (pintype "power_in"))
      (node (ref "D9") (pin "2") (pinfunction "OSCO_2") (pintype "passive"))
      (node (ref "Z2") (pin "2") (pinfunction "2_2") (pintype "passive"))
    )
    (net (code "15") (name "/VCC3V3_SYS") (class "Default")
      (node (ref "C100") (pin "1") (pinfunction "1_1") (pintype "power_in"))
      (node (ref "C101") (pin "1") (pinfunction "1_1") (pintype "power_in"))
      (node (ref "C120") (pin "1") (pinfunction "1_1") (pintype "power_in"))
      (node (ref "C121") (pin "1") (pinfunction "1_1") (pintype "power_in"))
      (node (ref "C82") (pin "1") (pinfunction "1_1") (pintype "power_in"))
      (node (ref "D10") (pin "4") (pinfunction "IN_4") (pintype "passive"))
      (node (ref "D7") (pin "1") (pinfunction "VIN_1") (pintype "passive"))
      (node (ref "R31") (pin "1") (pinfunction "1_1") (pintype "passive"))
      (node (ref "R53") (pin "1") (pinfunction "1_1") (pintype "passive"))
      (node (ref "VT1") (pin "2") (pinfunction "S_2") (pintype "passive"))
    )
    (net (code "16") (name "/VCC5V0_SYS") (class "Default")
      (node (ref "C108") (pin "1") (pinfunction "1_1") (pintype "power_in"))
      (node (ref "C109") (pin "1") (pinfunction "1_1") (pintype "power_in"))
      (node (ref "C83") (pin "1") (pinfunction "1_1") (pintype "power_in"))
      (node (ref "C84") (pin "1") (pinfunction "1_1") (pintype "power_in"))
      (node (ref "C85") (pin "1") (pinfunction "1_1") (pintype "power_in"))
      (node (ref "C93") (pin "1") (pinfunction "1_1") (pintype "power_in"))
      (node (ref "C94") (pin "1") (pinfunction "1_1") (pintype "power_in"))
      (node (ref "C95") (pin "1") (pinfunction "1_1") (pintype "power_in"))
      (node (ref "D5") (pin "D1") (pinfunction "VIN_D1") (pintype "passive"))
      (node (ref "D5") (pin "D2") (pinfunction "VIN_D2") (pintype "passive"))
      (node (ref "D5") (pin "E1") (pinfunction "VIN_E1") (pintype "passive"))
      (node (ref "D5") (pin "E2") (pinfunction "VIN_E2") (pintype "passive"))
      (node (ref "D6") (pin "D1") (pinfunction "VIN_D1") (pintype "passive"))
      (node (ref "D6") (pin "D2") (pinfunction "VIN_D2") (pintype "passive"))
      (node (ref "D6") (pin "E1") (pinfunction "VIN_E1") (pintype "passive"))
      (node (ref "D6") (pin "E2") (pinfunction "VIN_E2") (pintype "passive"))
      (node (ref "D8") (pin "4") (pinfunction "IN_4") (pintype "passive"))
    )
    (net (code "17") (name "/VCCA_0V9") (class "Default")
      (node (ref "C119") (pin "1") (pinfunction "1_1") (pintype "power_in"))
      (node (ref "C122") (pin "1") (pinfunction "1_1") (pintype "power_in"))
      (node (ref "C123") (pin "1") (pinfunction "1_1") (pintype "power_in"))
      (node (ref "L11") (pin "1") (pinfunction "1_1") (pintype "passive"))
      (node (ref "R52") (pin "2") (pinfunction "2_2") (pintype "passive"))
    )
    (net (code "18") (name "/VCCA_1V8") (class "Default")
      (node (ref "R51") (pin "2") (pinfunction "2_2") (pintype "passive"))
    )
    (net (code "19") (name "/VCC_1V8") (class "Default")
      (node (ref "R34") (pin "2") (pinfunction "2_2") (pintype "passive"))
      (node (ref "R37") (pin "2") (pinfunction "2_2") (pintype "passive"))
      (node (ref "R42") (pin "2") (pinfunction "2_2") (pintype "passive"))
      (node (ref "R48") (pin "1") (pinfunction "1_1") (pintype "passive"))
    )
    (net (code "20") (name "/VCC_3V0") (class "Default")
      (node (ref "R49") (pin "1") (pinfunction "1_1") (pintype "passive"))
    )
    (net (code "21") (name "/VCC_EFUSE") (class "Default")
      (node (ref "C103") (pin "1") (pinfunction "1_1") (pintype "power_in"))
      (node (ref "C104") (pin "1") (pinfunction "1_1") (pintype "power_in"))
      (node (ref "C105") (pin "1") (pinfunction "1_1") (pintype "power_in"))
      (node (ref "D7") (pin "5") (pinfunction "VOUT_5") (pintype "passive"))
    )
    (net (code "22") (name "/VCC_EXT_RTC") (class "Default")
      (node (ref "C117") (pin "1") (pinfunction "1_1") (pintype "power_in"))
      (node (ref "C118") (pin "1") (pinfunction "1_1") (pintype "power_in"))
      (node (ref "D9") (pin "8") (pinfunction "VDD_8") (pintype "passive"))
      (node (ref "R50") (pin "1") (pinfunction "1_1") (pintype "passive"))
    )
    (net (code "23") (name "/VDD_CPU_B") (class "Default")
      (node (ref "C107") (pin "1") (pinfunction "1_1") (pintype "power_in"))
      (node (ref "C96") (pin "2") (pinfunction "2_2") (pintype "power_in"))
      (node (ref "C97") (pin "2") (pinfunction "2_2") (pintype "power_in"))
      (node (ref "C98") (pin "2") (pinfunction "2_2") (pintype "power_in"))
      (node (ref "C99") (pin "2") (pinfunction "2_2") (pintype "power_in"))
      (node (ref "L9") (pin "1") (pinfunction "1_1") (pintype "passive"))
      (node (ref "R38") (pin "2") (pinfunction "2_2") (pintype "passive"))
    )
    (net (code "24") (name "/VDD_CPU_B_FB") (class "Default")
      (node (ref "D6") (pin "A4") (pinfunction "VOUT_A4") (pintype "passive"))
      (node (ref "R38") (pin "1") (pinfunction "1_1") (pintype "passive"))
    )
    (net (code "25") (name "/VDD_GPU") (class "Default")
      (node (ref "C87") (pin "2") (pinfunction "2_2") (pintype "power_in"))
      (node (ref "C88") (pin "2") (pinfunction "2_2") (pintype "power_in"))
      (node (ref "C89") (pin "2") (pinfunction "2_2") (pintype "power_in"))
      (node (ref "C90") (pin "2") (pinfunction "2_2") (pintype "power_in"))
      (node (ref "C92") (pin "1") (pinfunction "1_1") (pintype "power_in"))
      (node (ref "L8") (pin "1") (pinfunction "1_1") (pintype "passive"))
      (node (ref "R35") (pin "2") (pinfunction "2_2") (pintype "passive"))
    )
    (net (code "26") (name "/VDD_GPU_FB") (class "Default")
      (node (ref "D5") (pin "A4") (pinfunction "VOUT_A4") (pintype "passive"))
      (node (ref "R35") (pin "1") (pinfunction "1_1") (pintype "passive"))
    )
    (net (code "27") (name "/VDD_LOG") (class "Default")
      (node (ref "C111") (pin "2") (pinfunction "2_2") (pintype "power_in"))
      (node (ref "C112") (pin "1") (pinfunction "1_1") (pintype "power_in"))
      (node (ref "C113") (pin "1") (pinfunction "1_1") (pintype "power_in"))
      (node (ref "L10") (pin "1") (pinfunction "1_1") (pintype "passive"))
      (node (ref "R41") (pin "1") (pinfunction "1_1") (pintype "passive"))
      (node (ref "R41") (pin "2") (pinfunction "2_2") (pintype "passive"))
      (node (ref "R43") (pin "2") (pinfunction "2_2") (pintype "passive"))
    )
    (net (code "28") (name "/VPP_OTP") (class "Default")
      (node (ref "VT1") (pin "3") (pinfunction "D_3") (pintype "passive"))
    )
    (net (code "29") (name "Net-(C114-Pad1)") (class "Default")
      (node (ref "C114") (pin "1") (pinfunction "1_1") (pintype "power_in"))
      (node (ref "R44") (pin "2") (pinfunction "2_2") (pintype "passive"))
      (node (ref "R45") (pin "1") (pinfunction "1_1") (pintype "passive"))
      (node (ref "R46") (pin "2") (pinfunction "2_2") (pintype "passive"))
    )
    (net (code "30") (name "Net-(D5-EN)") (class "Default")
      (node (ref "C91") (pin "1") (pinfunction "1_1") (pintype "power_in"))
      (node (ref "D5") (pin "A2") (pinfunction "EN_A2") (pintype "passive"))
      (node (ref "R34") (pin "1") (pinfunction "1_1") (pintype "passive"))
    )
    (net (code "31") (name "Net-(D5-SW-PadD3)") (class "Default")
      (node (ref "D5") (pin "D3") (pinfunction "SW_D3") (pintype "passive"))
      (node (ref "D5") (pin "D4") (pinfunction "SW_D4") (pintype "passive"))
      (node (ref "D5") (pin "E3") (pinfunction "SW_E3") (pintype "passive"))
      (node (ref "D5") (pin "E4") (pinfunction "SW_E4") (pintype "passive"))
      (node (ref "L8") (pin "2") (pinfunction "2_2") (pintype "passive"))
    )
    (net (code "32") (name "Net-(D6-EN)") (class "Default")
      (node (ref "C106") (pin "1") (pinfunction "1_1") (pintype "power_in"))
      (node (ref "D6") (pin "A2") (pinfunction "EN_A2") (pintype "passive"))
      (node (ref "R37") (pin "1") (pinfunction "1_1") (pintype "passive"))
    )
    (net (code "33") (name "Net-(D6-SW-PadD3)") (class "Default")
      (node (ref "D6") (pin "D3") (pinfunction "SW_D3") (pintype "passive"))
      (node (ref "D6") (pin "D4") (pinfunction "SW_D4") (pintype "passive"))
      (node (ref "D6") (pin "E3") (pinfunction "SW_E3") (pintype "passive"))
      (node (ref "D6") (pin "E4") (pinfunction "SW_E4") (pintype "passive"))
      (node (ref "L9") (pin "2") (pinfunction "2_2") (pintype "passive"))
    )
    (net (code "34") (name "Net-(D7-CE)") (class "Default")
      (node (ref "D7") (pin "3") (pinfunction "CE_3") (pintype "passive"))
      (node (ref "R40") (pin "1") (pinfunction "1_1") (pintype "passive"))
    )
    (net (code "35") (name "Net-(D7-NC)") (class "Default")
      (node (ref "C102") (pin "1") (pinfunction "1_1") (pintype "power_in"))
      (node (ref "D7") (pin "4") (pinfunction "NC_4") (pintype "passive"))
    )
    (net (code "36") (name "Net-(D8-EN)") (class "Default")
      (node (ref "C110") (pin "1") (pinfunction "1_1") (pintype "power_in"))
      (node (ref "D8") (pin "1") (pinfunction "EN_1") (pintype "passive"))
      (node (ref "R42") (pin "1") (pinfunction "1_1") (pintype "passive"))
    )
    (net (code "37") (name "Net-(D8-FB)") (class "Default")
      (node (ref "C113") (pin "2") (pinfunction "2_2") (pintype "power_in"))
      (node (ref "D8") (pin "5") (pinfunction "FB_5") (pintype "passive"))
      (node (ref "R43") (pin "1") (pinfunction "1_1") (pintype "passive"))
      (node (ref "R45") (pin "2") (pinfunction "2_2") (pintype "passive"))
      (node (ref "R47") (pin "2") (pinfunction "2_2") (pintype "passive"))
    )
    (net (code "38") (name "Net-(D8-LX)") (class "Default")
      (node (ref "D8") (pin "3") (pinfunction "LX_3") (pintype "passive"))
      (node (ref "L10") (pin "2") (pinfunction "2_2") (pintype "passive"))
    )
    (net (code "39") (name "Net-(D10-EN)") (class "Default")
      (node (ref "C124") (pin "1") (pinfunction "1_1") (pintype "power_in"))
      (node (ref "D10") (pin "1") (pinfunction "EN_1") (pintype "passive"))
      (node (ref "R53") (pin "2") (pinfunction "2_2") (pintype "passive"))
    )
    (net (code "40") (name "Net-(D10-FB)") (class "Default")
      (node (ref "C119") (pin "2") (pinfunction "2_2") (pintype "power_in"))
      (node (ref "D10") (pin "5") (pinfunction "FB_5") (pintype "passive"))
      (node (ref "R52") (pin "1") (pinfunction "1_1") (pintype "passive"))
      (node (ref "R54") (pin "2") (pinfunction "2_2") (pintype "passive"))
    )
    (net (code "41") (name "Net-(D10-LX)") (class "Default")
      (node (ref "D10") (pin "3") (pinfunction "LX_3") (pintype "passive"))
      (node (ref "L11") (pin "2") (pinfunction "2_2") (pintype "passive"))
    )
    (net (code "42") (name "Net-(VD8-C)") (class "Default")
      (node (ref "C86") (pin "2") (pinfunction "2_2") (pintype "power_in"))
      (node (ref "R32") (pin "2") (pinfunction "2_2") (pintype "passive"))
      (node (ref "VD8") (pin "2") (pinfunction "C_2") (pintype "passive"))
    )
    (net (code "43") (name "Net-(VD9-C)") (class "Default")
      (node (ref "R50") (pin "2") (pinfunction "2_2") (pintype "passive"))
      (node (ref "VD9") (pin "2") (pinfunction "C_2") (pintype "passive"))
    )
    (net (code "44") (name "Net-(VT1-G)") (class "Default")
      (node (ref "C82") (pin "2") (pinfunction "2_2") (pintype "power_in"))
      (node (ref "R31") (pin "2") (pinfunction "2_2") (pintype "passive"))
      (node (ref "VT1") (pin "1") (pinfunction "G_1") (pintype "passive"))
      (node (ref "VT2") (pin "3") (pinfunction "C_3") (pintype "passive"))
    )
    (net (code "45") (name "Net-(VT2-B)") (class "Default")
      (node (ref "R32") (pin "1") (pinfunction "1_1") (pintype "passive"))
      (node (ref "R33") (pin "2") (pinfunction "2_2") (pintype "passive"))
      (node (ref "VT2") (pin "1") (pinfunction "B_1") (pintype "passive"))
    )
    (net (code "46") (name "unconnected-(D9-CLKOUT-Pad7)") (class "Default")
      (node (ref "D9") (pin "7") (pinfunction "CLKOUT_7") (pintype "passive"))
    )
  )
)
